# 03_-_CONTROLLER.net
KiCad netlist of a schematic drawn in Altium Designer
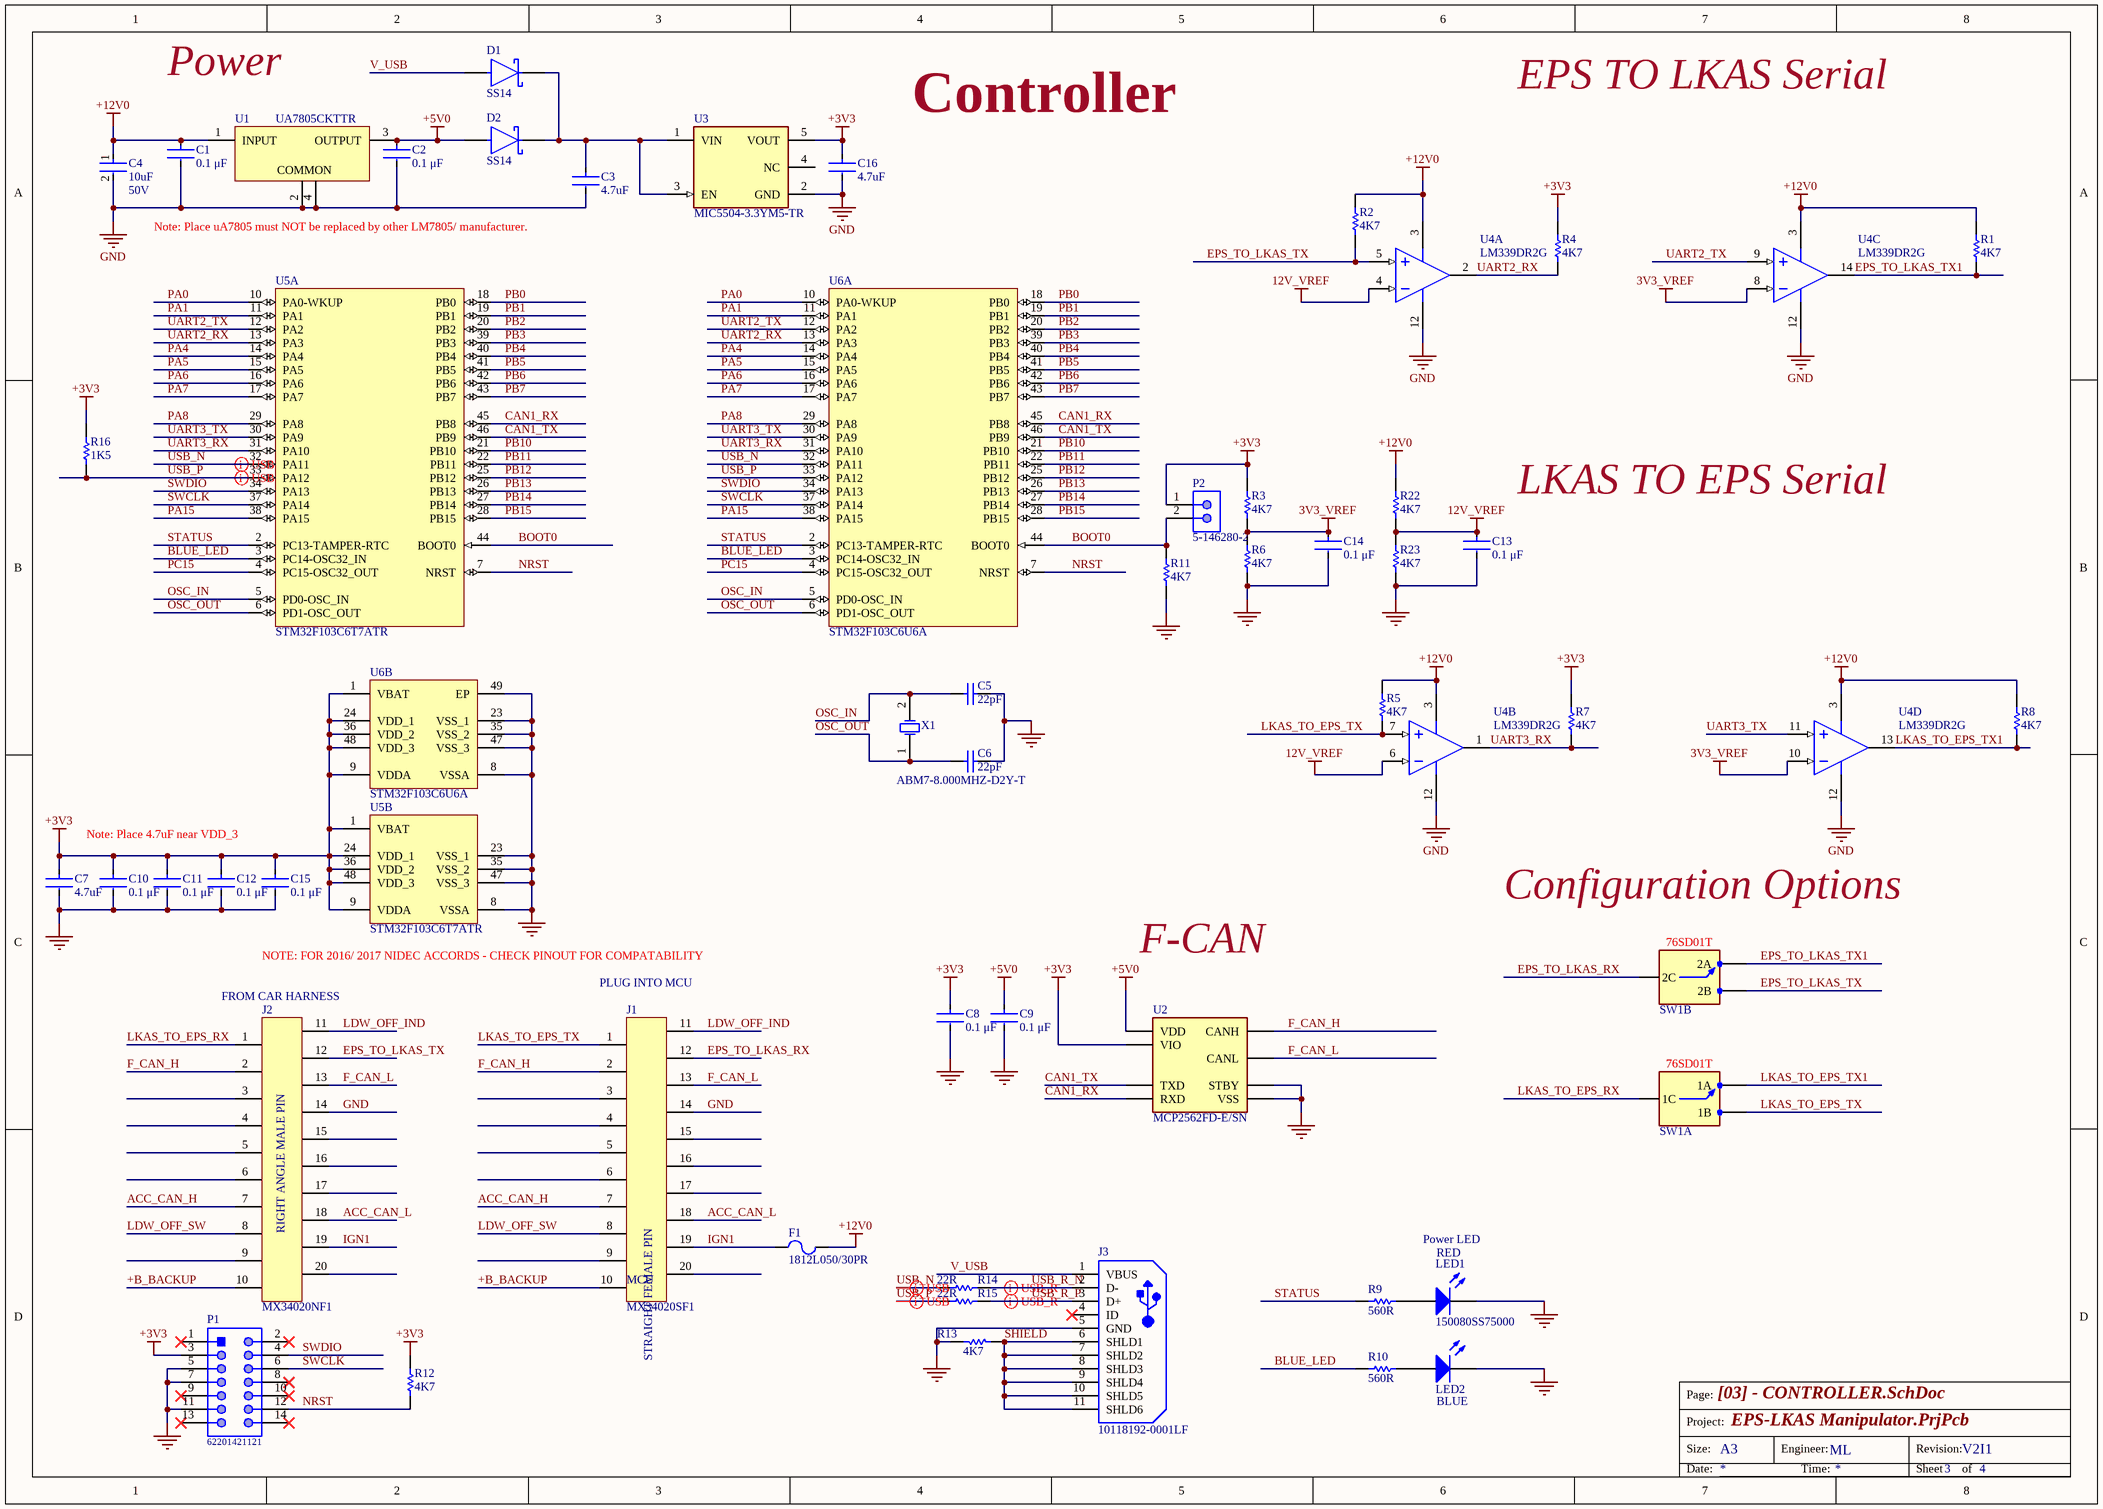
[diagram p0: [03] - CONTROLLER.SchDoc]

(export (version "E")
  (design (tool "Eeschema 10.0.6"))
  (components
    (comp (ref "C1")
      (value "C0603C104M3RACTU")
      (footprint "FP-C0603C-CF-MFG")
      (description "CAP CER 0.1UF 25V X7R 0603")
      (fields
        (field (name "CAPACITANCE") "0.1 μF")
        (field (name "OCTOPART") "https://octopart.com/c0603c104m3ractu-kemet-95914")
        (field (name "MANUFACTURER") "KEMET")
      )
      (libsource (lib "Altium Content Vault") (part "b4654b650e69147ec39a6b967a45e02"))
    )
    (comp (ref "C2")
      (value "C0603C104M3RACTU")
      (footprint "FP-C0603C-CF-MFG")
      (description "CAP CER 0.1UF 25V X7R 0603")
      (fields
        (field (name "CAPACITANCE") "0.1 μF")
        (field (name "OCTOPART") "https://octopart.com/c0603c104m3ractu-kemet-95914")
        (field (name "MANUFACTURER") "KEMET")
      )
      (libsource (lib "Altium Content Vault") (part "b4654b650e69147ec39a6b967a45e02"))
    )
    (comp (ref "C3")
      (value "CL10B475KQ8NQNC")
      (footprint "FP-CL10-IPC_C")
      (description "CAP CER 4.7UF 6.3V X7R 0603")
      (fields
        (field (name "TOLERANCE") "10%")
        (field (name "CAPACITANCE") "4.7uF")
        (field (name "OCTOPART") "https://octopart.com/cl10b475kq8nqnc-samsung-24957976")
      )
      (libsource (lib "Altium Content Vault") (part "11868f565c42a9108669ba33697ecf6"))
    )
    (comp (ref "C4")
      (value "10uF")
      (footprint "FP-CL31-IPC_C")
      (description "CAP CER 10UF 50V X5R 1206")
      (fields
        (field (name "TOLERANCE") "10%")
        (field (name "MANUFACTURER") "Samsung")
        (field (name "VOLTAGE") "50V")
      )
      (libsource (lib "") (part "11868f565c42a9108669ba33697ecf6_1"))
    )
    (comp (ref "C5")
      (value "GRM1885C1H220JA01D")
      (footprint "CAPC1608X90X35ML10T15")
      (description "Chip Capacitor, 22 pF, +/- 5%, 50 V, -55 to 125 degC, 0603 (1608 Metric), RoHS, Tape and Reel")
      (fields (field (name "CAPACITANCE") "22pF") (field (name "MANUFACTURER") "Murata"))
      (libsource (lib "Altium Content Vault") (part "CAP-NP-2"))
    )
    (comp (ref "C6")
      (value "GRM1885C1H220JA01D")
      (footprint "CAPC1608X90X35ML10T15")
      (description "Chip Capacitor, 22 pF, +/- 5%, 50 V, -55 to 125 degC, 0603 (1608 Metric), RoHS, Tape and Reel")
      (fields (field (name "CAPACITANCE") "22pF") (field (name "MANUFACTURER") "Murata"))
      (libsource (lib "Altium Content Vault") (part "CAP-NP-2"))
    )
    (comp (ref "C7")
      (value "CL10B475KQ8NQNC")
      (footprint "FP-CL10-IPC_C")
      (description "CAP CER 4.7UF 6.3V X7R 0603")
      (fields
        (field (name "TOLERANCE") "10%")
        (field (name "CAPACITANCE") "4.7uF")
        (field (name "OCTOPART") "https://octopart.com/cl10b475kq8nqnc-samsung-24957976")
      )
      (libsource (lib "Altium Content Vault") (part "11868f565c42a9108669ba33697ecf6"))
    )
    (comp (ref "C8")
      (value "C0603C104M3RACTU")
      (footprint "FP-C0603C-CF-MFG")
      (description "CAP CER 0.1UF 25V X7R 0603")
      (fields
        (field (name "CAPACITANCE") "0.1 μF")
        (field (name "OCTOPART") "https://octopart.com/c0603c104m3ractu-kemet-95914")
        (field (name "MANUFACTURER") "KEMET")
      )
      (libsource (lib "Altium Content Vault") (part "b4654b650e69147ec39a6b967a45e02"))
    )
    (comp (ref "C9")
      (value "C0603C104M3RACTU")
      (footprint "FP-C0603C-CF-MFG")
      (description "CAP CER 0.1UF 25V X7R 0603")
      (fields
        (field (name "CAPACITANCE") "0.1 μF")
        (field (name "OCTOPART") "https://octopart.com/c0603c104m3ractu-kemet-95914")
        (field (name "MANUFACTURER") "KEMET")
      )
      (libsource (lib "Altium Content Vault") (part "b4654b650e69147ec39a6b967a45e02"))
    )
    (comp (ref "C10")
      (value "C0603C104M3RACTU")
      (footprint "FP-C0603C-CF-MFG")
      (description "CAP CER 0.1UF 25V X7R 0603")
      (fields
        (field (name "CAPACITANCE") "0.1 μF")
        (field (name "OCTOPART") "https://octopart.com/c0603c104m3ractu-kemet-95914")
        (field (name "MANUFACTURER") "KEMET")
      )
      (libsource (lib "Altium Content Vault") (part "b4654b650e69147ec39a6b967a45e02"))
    )
    (comp (ref "C11")
      (value "C0603C104M3RACTU")
      (footprint "FP-C0603C-CF-MFG")
      (description "CAP CER 0.1UF 25V X7R 0603")
      (fields
        (field (name "CAPACITANCE") "0.1 μF")
        (field (name "OCTOPART") "https://octopart.com/c0603c104m3ractu-kemet-95914")
        (field (name "MANUFACTURER") "KEMET")
      )
      (libsource (lib "Altium Content Vault") (part "b4654b650e69147ec39a6b967a45e02"))
    )
    (comp (ref "C12")
      (value "C0603C104M3RACTU")
      (footprint "FP-C0603C-CF-MFG")
      (description "CAP CER 0.1UF 25V X7R 0603")
      (fields
        (field (name "CAPACITANCE") "0.1 μF")
        (field (name "OCTOPART") "https://octopart.com/c0603c104m3ractu-kemet-95914")
        (field (name "MANUFACTURER") "KEMET")
      )
      (libsource (lib "Altium Content Vault") (part "b4654b650e69147ec39a6b967a45e02"))
    )
    (comp (ref "C13")
      (value "C0603C104M3RACTU")
      (footprint "FP-C0603C-CF-MFG")
      (description "CAP CER 0.1UF 25V X7R 0603")
      (fields
        (field (name "CAPACITANCE") "0.1 μF")
        (field (name "OCTOPART") "https://octopart.com/c0603c104m3ractu-kemet-95914")
        (field (name "MANUFACTURER") "KEMET")
      )
      (libsource (lib "Altium Content Vault") (part "b4654b650e69147ec39a6b967a45e02"))
    )
    (comp (ref "C14")
      (value "C0603C104M3RACTU")
      (footprint "FP-C0603C-CF-MFG")
      (description "CAP CER 0.1UF 25V X7R 0603")
      (fields
        (field (name "CAPACITANCE") "0.1 μF")
        (field (name "OCTOPART") "https://octopart.com/c0603c104m3ractu-kemet-95914")
        (field (name "MANUFACTURER") "KEMET")
      )
      (libsource (lib "Altium Content Vault") (part "b4654b650e69147ec39a6b967a45e02"))
    )
    (comp (ref "C15")
      (value "C0603C104M3RACTU")
      (footprint "FP-C0603C-CF-MFG")
      (description "CAP CER 0.1UF 25V X7R 0603")
      (fields
        (field (name "CAPACITANCE") "0.1 μF")
        (field (name "OCTOPART") "https://octopart.com/c0603c104m3ractu-kemet-95914")
        (field (name "MANUFACTURER") "KEMET")
      )
      (libsource (lib "Altium Content Vault") (part "b4654b650e69147ec39a6b967a45e02"))
    )
    (comp (ref "C16")
      (value "CL10B475KQ8NQNC")
      (footprint "FP-CL10-IPC_C")
      (description "CAP CER 4.7UF 6.3V X7R 0603")
      (fields
        (field (name "TOLERANCE") "10%")
        (field (name "CAPACITANCE") "4.7uF")
        (field (name "OCTOPART") "https://octopart.com/cl10b475kq8nqnc-samsung-24957976")
      )
      (libsource (lib "Altium Content Vault") (part "11868f565c42a9108669ba33697ecf6"))
    )
    (comp (ref "D1")
      (value "SS14")
      (footprint "FP-403AE-MFG")
      (description "DIODE SCHOTTKY 40V 1A SMA")
      (fields
        (field (name "MANUFACTURER") "ON Semiconductor")
        (field (name "OCTOPART") "https://octopart.com/ss14-on+semiconductor-29205033")
      )
      (libsource (lib "Altium Content Vault") (part "360ad2f4ac25a952324d13796385471"))
    )
    (comp (ref "D2")
      (value "SS14")
      (footprint "FP-403AE-MFG")
      (description "DIODE SCHOTTKY 40V 1A SMA")
      (fields
        (field (name "MANUFACTURER") "ON Semiconductor")
        (field (name "OCTOPART") "https://octopart.com/ss14-on+semiconductor-29205033")
      )
      (libsource (lib "Altium Content Vault") (part "360ad2f4ac25a952324d13796385471"))
    )
    (comp (ref "F1")
      (value "1812L050/30PR")
      (footprint "LFUS-1812L05030PR_V")
      (description "PTC Resettable Fuse, 0.8 W, 30 V, -40 to 85 degC, 2-Pin SMD, RoHS, Tape and Reel")
      (fields (field (name "MANUFACTURER") "Littelfuse-Inc."))
      (libsource (lib "Altium Content Vault") (part "FUSE-2"))
    )
    (comp (ref "J1")
      (value "MX34020SF1")
      (footprint "MX34020SF1")
      (description "Automotive Connectors Sckt HOUSING 20P")
      (fields (field (name "MANUFACTURER") "JAE Electronics"))
      (libsource (lib "MCU_EPS") (part "MX34020SF1"))
    )
    (comp (ref "J2")
      (value "MX34020NF1")
      (footprint "MX34020NF1")
      (description "JAE MX34 Series, 2.2mm Pitch 20 Way 2 Row Right Angle PCB Header, Solder Termination, 3A")
      (fields (field (name "MANUFACTURER") "JAE Electronics"))
      (libsource (lib "MCU_EPS") (part "MX34020NF1"))
    )
    (comp (ref "J3")
      (value "10118192-0001LF")
      (footprint "FCI-10118192-0001LF-5_V")
      (description "Micro USB B Type Receptacle, -55 to 85 degC, 5-Pin SMD, RoHS, Tape and Reel")
      (fields (field (name "MANUFACTURER") "FCI"))
      (libsource (lib "Altium Content Vault") (part "USB-5-6SHLD"))
    )
    (comp (ref "LED1")
      (value "150080SS75000")
      (footprint "0805_A")
      (description "SMD mono-color Chip LED, WL-SMCW, Super Red")
      (fields (field (name "MANUFACTURER") "Wuerth Elektronik"))
      (libsource (lib "Altium Content Vault") (part "WE-LED_K1A2-2"))
    )
    (comp (ref "LED2")
      (value "150080BS75000")
      (footprint "0805_A")
      (description "SMD mono-color Chip LED, WL-SMCW, Blue")
      (fields (field (name "MANUFACTURER") "Wuerth Elektronik"))
      (libsource (lib "Altium Content Vault") (part "WE-LED_K1A2-2"))
    )
    (comp (ref "P1")
      (value "62201421121")
      (footprint "62201421121")
      (description "THT Vertical Pin Header WR-PHD, Pitch 1.27 mm, Dual Row, 14 pins")
      (fields (field (name "MANUFACTURER") "Wurth Elektronik") (field (name "PUBLISHER") "WurthElektronik"))
      (libsource (lib "Altium Content Vault") (part "WE-CN-2P-M-R14"))
    )
    (comp (ref "P2")
      (value "5-146280-2")
      (footprint "TECO-5-146280-2_V")
      (fields (field (name "MANUFACTURER") "TE Connectivity"))
      (libsource (lib "Altium Content Vault") (part "CN-1P-M-R2"))
    )
    (comp (ref "R1")
      (value "4K7")
      (footprint "R0603")
      (description "Res Thick Film 0603 4.7K Ohm 1% 1/10W 100ppm/C Molded SMD SMD Paper T/R")
      (fields
        (field (name "MANUFACTURER") "Stackpole Electronics")
        (field (name "MANUFACTURER PART NUMBER") "RMCF0603FT4K70")
      )
      (libsource (lib "LKAS_EPS") (part "RMCF0603FT4K70"))
    )
    (comp (ref "R2")
      (value "4K7")
      (footprint "R0603")
      (description "Res Thick Film 0603 4.7K Ohm 1% 1/10W 100ppm/C Molded SMD SMD Paper T/R")
      (fields
        (field (name "MANUFACTURER") "Stackpole Electronics")
        (field (name "MANUFACTURER PART NUMBER") "RMCF0603FT4K70")
      )
      (libsource (lib "LKAS_EPS") (part "RMCF0603FT4K70"))
    )
    (comp (ref "R3")
      (value "4K7")
      (footprint "R0603")
      (description "Res Thick Film 0603 4.7K Ohm 1% 1/10W 100ppm/C Molded SMD SMD Paper T/R")
      (fields
        (field (name "MANUFACTURER") "Stackpole Electronics")
        (field (name "MANUFACTURER PART NUMBER") "RMCF0603FT4K70")
      )
      (libsource (lib "LKAS_EPS") (part "RMCF0603FT4K70"))
    )
    (comp (ref "R4")
      (value "4K7")
      (footprint "R0603")
      (description "Res Thick Film 0603 4.7K Ohm 1% 1/10W 100ppm/C Molded SMD SMD Paper T/R")
      (fields
        (field (name "MANUFACTURER") "Stackpole Electronics")
        (field (name "MANUFACTURER PART NUMBER") "RMCF0603FT4K70")
      )
      (libsource (lib "LKAS_EPS") (part "RMCF0603FT4K70"))
    )
    (comp (ref "R5")
      (value "4K7")
      (footprint "R0603")
      (description "Res Thick Film 0603 4.7K Ohm 1% 1/10W 100ppm/C Molded SMD SMD Paper T/R")
      (fields
        (field (name "MANUFACTURER") "Stackpole Electronics")
        (field (name "MANUFACTURER PART NUMBER") "RMCF0603FT4K70")
      )
      (libsource (lib "LKAS_EPS") (part "RMCF0603FT4K70"))
    )
    (comp (ref "R6")
      (value "4K7")
      (footprint "R0603")
      (description "Res Thick Film 0603 4.7K Ohm 1% 1/10W 100ppm/C Molded SMD SMD Paper T/R")
      (fields
        (field (name "MANUFACTURER") "Stackpole Electronics")
        (field (name "MANUFACTURER PART NUMBER") "RMCF0603FT4K70")
      )
      (libsource (lib "LKAS_EPS") (part "RMCF0603FT4K70"))
    )
    (comp (ref "R7")
      (value "4K7")
      (footprint "R0603")
      (description "Res Thick Film 0603 4.7K Ohm 1% 1/10W 100ppm/C Molded SMD SMD Paper T/R")
      (fields
        (field (name "MANUFACTURER") "Stackpole Electronics")
        (field (name "MANUFACTURER PART NUMBER") "RMCF0603FT4K70")
      )
      (libsource (lib "LKAS_EPS") (part "RMCF0603FT4K70"))
    )
    (comp (ref "R8")
      (value "4K7")
      (footprint "R0603")
      (description "Res Thick Film 0603 4.7K Ohm 1% 1/10W 100ppm/C Molded SMD SMD Paper T/R")
      (fields
        (field (name "MANUFACTURER") "Stackpole Electronics")
        (field (name "MANUFACTURER PART NUMBER") "RMCF0603FT4K70")
      )
      (libsource (lib "LKAS_EPS") (part "RMCF0603FT4K70"))
    )
    (comp (ref "R9")
      (value "RC0603FR-07560RL")
      (footprint "RESC1608X55X25ML10T15")
      (description "Chip Resistor, 560 Ohm, +/- 1%, 0.1 W, -55 to 155 degC, 0603 (1608 Metric), RoHS, Tape and Reel")
      (fields (field (name "RESISTANCE") "560R") (field (name "TOLERANCE") "1%"))
      (libsource (lib "Altium Content Vault") (part "RES-2"))
    )
    (comp (ref "R10")
      (value "RC0603FR-07560RL")
      (footprint "RESC1608X55X25ML10T15")
      (description "Chip Resistor, 560 Ohm, +/- 1%, 0.1 W, -55 to 155 degC, 0603 (1608 Metric), RoHS, Tape and Reel")
      (fields (field (name "RESISTANCE") "560R") (field (name "TOLERANCE") "1%"))
      (libsource (lib "Altium Content Vault") (part "RES-2"))
    )
    (comp (ref "R11")
      (value "4K7")
      (footprint "R0603")
      (description "Res Thick Film 0603 4.7K Ohm 1% 1/10W 100ppm/C Molded SMD SMD Paper T/R")
      (fields
        (field (name "MANUFACTURER") "Stackpole Electronics")
        (field (name "MANUFACTURER PART NUMBER") "RMCF0603FT4K70")
      )
      (libsource (lib "LKAS_EPS") (part "RMCF0603FT4K70"))
    )
    (comp (ref "R12")
      (value "4K7")
      (footprint "R0603")
      (description "Res Thick Film 0603 4.7K Ohm 1% 1/10W 100ppm/C Molded SMD SMD Paper T/R")
      (fields
        (field (name "MANUFACTURER") "Stackpole Electronics")
        (field (name "MANUFACTURER PART NUMBER") "RMCF0603FT4K70")
      )
      (libsource (lib "LKAS_EPS") (part "RMCF0603FT4K70"))
    )
    (comp (ref "R13")
      (value "4K7")
      (footprint "R0603")
      (description "Res Thick Film 0603 4.7K Ohm 1% 1/10W 100ppm/C Molded SMD SMD Paper T/R")
      (fields
        (field (name "MANUFACTURER") "Stackpole Electronics")
        (field (name "MANUFACTURER PART NUMBER") "RMCF0603FT4K70")
      )
      (libsource (lib "LKAS_EPS") (part "RMCF0603FT4K70"))
    )
    (comp (ref "R14")
      (value "22R")
      (footprint "RESC1609X50X30ML10T20")
      (fields (field (name "MANUFACTURER") "Vishay Dale") (field (name "PART NUMBER") "CRCW060322R0JNTA"))
      (libsource (lib "Altium Content Vault") (part "RES"))
    )
    (comp (ref "R15")
      (value "22R")
      (footprint "RESC1609X50X30ML10T20")
      (fields (field (name "MANUFACTURER") "Vishay Dale") (field (name "PART NUMBER") "CRCW060322R0JNTA"))
      (libsource (lib "Altium Content Vault") (part "RES"))
    )
    (comp (ref "R16")
      (value "CRCW06031K50FKTA")
      (footprint "RESC1609X50X30ML10T20")
      (fields (field (name "MANUFACTURER") "Vishay Dale") (field (name "RES") "1K5"))
      (libsource (lib "Altium Content Vault") (part "RES"))
    )
    (comp (ref "R22")
      (value "4K7")
      (footprint "R0603")
      (description "Res Thick Film 0603 4.7K Ohm 1% 1/10W 100ppm/C Molded SMD SMD Paper T/R")
      (fields
        (field (name "MANUFACTURER") "Stackpole Electronics")
        (field (name "MANUFACTURER PART NUMBER") "RMCF0603FT4K70")
      )
      (libsource (lib "LKAS_EPS") (part "RMCF0603FT4K70"))
    )
    (comp (ref "R23")
      (value "4K7")
      (footprint "R0603")
      (description "Res Thick Film 0603 4.7K Ohm 1% 1/10W 100ppm/C Molded SMD SMD Paper T/R")
      (fields
        (field (name "MANUFACTURER") "Stackpole Electronics")
        (field (name "MANUFACTURER PART NUMBER") "RMCF0603FT4K70")
      )
      (libsource (lib "LKAS_EPS") (part "RMCF0603FT4K70"))
    )
    (comp (ref "SW1")
      (value "76STC02T")
      (footprint "76STC02T")
      (description "SWITCH TOGGLE DIP SPDT 150MA 30V\r\nWIRED:\r\n1  2  3\r\n4  5  6")
      (fields (field (name "MANUFACTURER") "Grayhill"))
      (libsource (lib "LKAS_EPS") (part "76STC02T"))
    )
    (comp (ref "U1")
      (value "UA7805CKTTR")
      (footprint "KTT0003A_V")
      (fields (field (name "TOLERANCE") "1%"))
      (libsource (lib "Altium Content Vault") (part "TI-UA78XX-KTT-3"))
    )
    (comp (ref "U2")
      (value "MCP2562FD-E/SN")
      (footprint "MCP2561")
      (description "8 SOIC 3.90mm(.150in) TUBECAN Flexible Data Rate Transceiver")
      (fields (field (name "MANUFACTURER") "Microchip"))
      (libsource (lib "MCU_EPS") (part "MCP2562FD-E/SN"))
    )
    (comp (ref "U3")
      (value "MIC5504-3.3YM5-TR")
      (footprint "FP-SOT23-5LD-PL-1-MFG")
      (description "IC REG LINEAR 3.3V 300MA SOT23-5")
      (libsource (lib "Altium Content Vault") (part "96048095611b4a9579e1e315950d302"))
    )
    (comp (ref "U4")
      (value "LM339DR2G")
      (footprint "ONSC-SOIC-14-751A-03_V")
      (description "Single Supply Quad Comparators, 0 to 70 degC, 14-Pin SOIC, Pb-Free, Tape and Reel")
      (fields (field (name "MANUFACTURER") "On Semiconductor"))
      (libsource (lib "Altium Content Vault") (part "ONSC-LM239_LM339_LM2901_NCV2901_MC3302_LMV339-14"))
    )
    (comp (ref "U5")
      (value "STM32F103C6T7ATR")
      (footprint "STM-LQFP48_L")
      (libsource (lib "Altium Content Vault") (part "MC-ARM-STM32F103X4_6-SQ48"))
    )
    (comp (ref "U6")
      (value "STM32F103C6U6A")
      (footprint "STM-UFQFPN48_M")
      (libsource (lib "Altium Content Vault") (part "MC-ARM-STM32F103X4_6-SQ49"))
    )
    (comp (ref "X1")
      (value "ABM7-8.000MHZ-D2Y-T")
      (footprint "ABRA-ABM7-2_V")
      (description "Microprocessor Crystal, 8 MHz, 18 PF, -40 to 85 degC, 2-Pin SMD, RoHS, Tape and Reel")
      (fields (field (name "MANUFACTURER") "Abracon"))
      (libsource (lib "Altium Content Vault") (part "XTAL_1-2-2"))
    )
  )
  (nets
    (net (code "1") (name "+3V3") (class "Default")
      (node (ref "C10") (pin "1") (pinfunction "1_1") (pintype "passive"))
      (node (ref "C11") (pin "1") (pinfunction "1_1") (pintype "passive"))
      (node (ref "C12") (pin "1") (pinfunction "1_1") (pintype "passive"))
      (node (ref "C15") (pin "1") (pinfunction "1_1") (pintype "passive"))
      (node (ref "C16") (pin "1") (pinfunction "1_1") (pintype "passive"))
      (node (ref "C7") (pin "1") (pinfunction "1_1") (pintype "passive"))
      (node (ref "C8") (pin "1") (pinfunction "1_1") (pintype "passive"))
      (node (ref "P1") (pin "3") (pinfunction "3_3") (pintype "passive"))
      (node (ref "P2") (pin "1") (pinfunction "1_1") (pintype "passive"))
      (node (ref "R12") (pin "2") (pinfunction "2_2") (pintype "passive"))
      (node (ref "R16") (pin "2") (pinfunction "2_2") (pintype "passive"))
      (node (ref "R3") (pin "2") (pinfunction "2_2") (pintype "passive"))
      (node (ref "R4") (pin "2") (pinfunction "2_2") (pintype "passive"))
      (node (ref "R7") (pin "2") (pinfunction "2_2") (pintype "passive"))
      (node (ref "U2") (pin "5") (pinfunction "VIO_5") (pintype "passive"))
      (node (ref "U3") (pin "5") (pinfunction "VOUT_5") (pintype "power_in"))
      (node (ref "U5") (pin "1") (pinfunction "VBAT_1") (pintype "power_in"))
      (node (ref "U5") (pin "24") (pinfunction "VDD_1_24") (pintype "power_in"))
      (node (ref "U5") (pin "36") (pinfunction "VDD_2_36") (pintype "power_in"))
      (node (ref "U5") (pin "48") (pinfunction "VDD_3_48") (pintype "power_in"))
      (node (ref "U5") (pin "9") (pinfunction "VDDA_9") (pintype "power_in"))
      (node (ref "U6") (pin "1") (pinfunction "VBAT_1") (pintype "power_in"))
      (node (ref "U6") (pin "24") (pinfunction "VDD_1_24") (pintype "power_in"))
      (node (ref "U6") (pin "36") (pinfunction "VDD_2_36") (pintype "power_in"))
      (node (ref "U6") (pin "48") (pinfunction "VDD_3_48") (pintype "power_in"))
      (node (ref "U6") (pin "9") (pinfunction "VDDA_9") (pintype "power_in"))
    )
    (net (code "2") (name "+5V0") (class "Default")
      (node (ref "C2") (pin "1") (pinfunction "1_1") (pintype "passive"))
      (node (ref "C9") (pin "1") (pinfunction "1_1") (pintype "passive"))
      (node (ref "D2") (pin "1") (pinfunction "A_1") (pintype "passive"))
      (node (ref "U1") (pin "3") (pinfunction "OUTPUT_3") (pintype "power_in"))
      (node (ref "U2") (pin "3") (pinfunction "VDD_3") (pintype "passive"))
    )
    (net (code "3") (name "+12V0") (class "Default")
      (node (ref "C1") (pin "1") (pinfunction "1_1") (pintype "passive"))
      (node (ref "C4") (pin "1") (pinfunction "1_1") (pintype "passive"))
      (node (ref "F1") (pin "2") (pinfunction "2_2") (pintype "passive"))
      (node (ref "R1") (pin "2") (pinfunction "2_2") (pintype "passive"))
      (node (ref "R2") (pin "2") (pinfunction "2_2") (pintype "passive"))
      (node (ref "R22") (pin "2") (pinfunction "2_2") (pintype "passive"))
      (node (ref "R5") (pin "2") (pinfunction "2_2") (pintype "passive"))
      (node (ref "R8") (pin "2") (pinfunction "2_2") (pintype "passive"))
      (node (ref "U1") (pin "1") (pinfunction "INPUT_1") (pintype "power_in"))
      (node (ref "U4") (pin "3") (pinfunction "VCC_3") (pintype "power_in"))
    )
    (net (code "4") (name "/+B_BACKUP") (class "Default")
      (node (ref "J1") (pin "10") (pinfunction "10_10") (pintype "passive"))
      (node (ref "J2") (pin "10") (pinfunction "10_10") (pintype "passive"))
    )
    (net (code "5") (name "/ACC_CAN_H") (class "Default")
      (node (ref "J1") (pin "7") (pinfunction "7_7") (pintype "passive"))
      (node (ref "J2") (pin "7") (pinfunction "7_7") (pintype "passive"))
    )
    (net (code "6") (name "/ACC_CAN_L") (class "Default")
      (node (ref "J1") (pin "18") (pinfunction "18_18") (pintype "passive"))
      (node (ref "J2") (pin "18") (pinfunction "18_18") (pintype "passive"))
    )
    (net (code "7") (name "/BLUE_LED") (class "Default")
      (node (ref "R10") (pin "1") (pinfunction "1_1") (pintype "passive"))
      (node (ref "U5") (pin "3") (pinfunction "PC14-OSC32_IN_3") (pintype "bidirectional"))
      (node (ref "U6") (pin "3") (pinfunction "PC14-OSC32_IN_3") (pintype "bidirectional"))
    )
    (net (code "8") (name "/BOOT0") (class "Default")
      (node (ref "P2") (pin "2") (pinfunction "2_2") (pintype "passive"))
      (node (ref "R11") (pin "2") (pinfunction "2_2") (pintype "passive"))
      (node (ref "U5") (pin "44") (pinfunction "BOOT0_44") (pintype "input"))
      (node (ref "U6") (pin "44") (pinfunction "BOOT0_44") (pintype "input"))
    )
    (net (code "9") (name "/CAN1_RX") (class "Default")
      (node (ref "U2") (pin "4") (pinfunction "RXD_4") (pintype "passive"))
      (node (ref "U5") (pin "45") (pinfunction "PB8_45") (pintype "bidirectional"))
      (node (ref "U6") (pin "45") (pinfunction "PB8_45") (pintype "bidirectional"))
    )
    (net (code "10") (name "/CAN1_TX") (class "Default")
      (node (ref "U2") (pin "1") (pinfunction "TXD_1") (pintype "passive"))
      (node (ref "U5") (pin "46") (pinfunction "PB9_46") (pintype "bidirectional"))
      (node (ref "U6") (pin "46") (pinfunction "PB9_46") (pintype "bidirectional"))
    )
    (net (code "11") (name "/EPS_TO_LKAS_RX") (class "Default")
      (node (ref "J1") (pin "12") (pinfunction "12_12") (pintype "passive"))
      (node (ref "SW1") (pin "C2") (pinfunction "2C_C2") (pintype "passive"))
    )
    (net (code "12") (name "/EPS_TO_LKAS_TX") (class "Default")
      (node (ref "J2") (pin "12") (pinfunction "12_12") (pintype "passive"))
      (node (ref "R2") (pin "1") (pinfunction "1_1") (pintype "passive"))
      (node (ref "SW1") (pin "2B") (pinfunction "2B_2B") (pintype "passive"))
      (node (ref "U4") (pin "5") (pinfunction "IN1+_5") (pintype "input"))
    )
    (net (code "13") (name "/EPS_TO_LKAS_TX1") (class "Default")
      (node (ref "R1") (pin "1") (pinfunction "1_1") (pintype "passive"))
      (node (ref "SW1") (pin "2A") (pinfunction "2A_2A") (pintype "passive"))
      (node (ref "U4") (pin "14") (pinfunction "OUT3_14") (pintype "open_collector"))
    )
    (net (code "14") (name "/F_CAN_H") (class "Default")
      (node (ref "J1") (pin "2") (pinfunction "2_2") (pintype "passive"))
      (node (ref "J2") (pin "2") (pinfunction "2_2") (pintype "passive"))
      (node (ref "U2") (pin "7") (pinfunction "CANH_7") (pintype "passive"))
    )
    (net (code "15") (name "/F_CAN_L") (class "Default")
      (node (ref "J1") (pin "13") (pinfunction "13_13") (pintype "passive"))
      (node (ref "J2") (pin "13") (pinfunction "13_13") (pintype "passive"))
      (node (ref "U2") (pin "6") (pinfunction "CANL_6") (pintype "passive"))
    )
    (net (code "16") (name "/IGN1") (class "Default")
      (node (ref "F1") (pin "1") (pinfunction "1_1") (pintype "passive"))
      (node (ref "J1") (pin "19") (pinfunction "19_19") (pintype "passive"))
      (node (ref "J2") (pin "19") (pinfunction "19_19") (pintype "passive"))
    )
    (net (code "17") (name "/LDW_OFF_IND") (class "Default")
      (node (ref "J1") (pin "11") (pinfunction "11_11") (pintype "passive"))
      (node (ref "J2") (pin "11") (pinfunction "11_11") (pintype "passive"))
    )
    (net (code "18") (name "/LDW_OFF_SW") (class "Default")
      (node (ref "J1") (pin "8") (pinfunction "8_8") (pintype "passive"))
      (node (ref "J2") (pin "8") (pinfunction "8_8") (pintype "passive"))
    )
    (net (code "19") (name "/LKAS_TO_EPS_RX") (class "Default")
      (node (ref "J2") (pin "1") (pinfunction "1_1") (pintype "passive"))
      (node (ref "SW1") (pin "C1") (pinfunction "1C_C1") (pintype "passive"))
    )
    (net (code "20") (name "/LKAS_TO_EPS_TX") (class "Default")
      (node (ref "J1") (pin "1") (pinfunction "1_1") (pintype "passive"))
      (node (ref "R5") (pin "1") (pinfunction "1_1") (pintype "passive"))
      (node (ref "SW1") (pin "1B") (pinfunction "1B_1B") (pintype "passive"))
      (node (ref "U4") (pin "7") (pinfunction "IN2+_7") (pintype "input"))
    )
    (net (code "21") (name "/LKAS_TO_EPS_TX1") (class "Default")
      (node (ref "R8") (pin "1") (pinfunction "1_1") (pintype "passive"))
      (node (ref "SW1") (pin "1A") (pinfunction "1A_1A") (pintype "passive"))
      (node (ref "U4") (pin "13") (pinfunction "OUT4_13") (pintype "open_collector"))
    )
    (net (code "22") (name "/NRST") (class "Default")
      (node (ref "P1") (pin "12") (pinfunction "12_12") (pintype "passive"))
      (node (ref "R12") (pin "1") (pinfunction "1_1") (pintype "passive"))
      (node (ref "U5") (pin "7") (pinfunction "NRST_7") (pintype "bidirectional"))
      (node (ref "U6") (pin "7") (pinfunction "NRST_7") (pintype "bidirectional"))
    )
    (net (code "23") (name "/OSC_IN") (class "Default")
      (node (ref "C5") (pin "1") (pinfunction "1_1") (pintype "passive"))
      (node (ref "U5") (pin "5") (pinfunction "PD0-OSC_IN_5") (pintype "bidirectional"))
      (node (ref "U6") (pin "5") (pinfunction "PD0-OSC_IN_5") (pintype "bidirectional"))
      (node (ref "X1") (pin "2") (pinfunction "X2_2") (pintype "passive"))
    )
    (net (code "24") (name "/OSC_OUT") (class "Default")
      (node (ref "C6") (pin "1") (pinfunction "1_1") (pintype "passive"))
      (node (ref "U5") (pin "6") (pinfunction "PD1-OSC_OUT_6") (pintype "bidirectional"))
      (node (ref "U6") (pin "6") (pinfunction "PD1-OSC_OUT_6") (pintype "bidirectional"))
      (node (ref "X1") (pin "1") (pinfunction "X1_1") (pintype "passive"))
    )
    (net (code "25") (name "/PA0") (class "Default")
      (node (ref "U5") (pin "10") (pinfunction "PA0-WKUP_10") (pintype "bidirectional"))
      (node (ref "U6") (pin "10") (pinfunction "PA0-WKUP_10") (pintype "bidirectional"))
    )
    (net (code "26") (name "/PA1") (class "Default")
      (node (ref "U5") (pin "11") (pinfunction "PA1_11") (pintype "bidirectional"))
      (node (ref "U6") (pin "11") (pinfunction "PA1_11") (pintype "bidirectional"))
    )
    (net (code "27") (name "/PA4") (class "Default")
      (node (ref "U5") (pin "14") (pinfunction "PA4_14") (pintype "bidirectional"))
      (node (ref "U6") (pin "14") (pinfunction "PA4_14") (pintype "bidirectional"))
    )
    (net (code "28") (name "/PA5") (class "Default")
      (node (ref "U5") (pin "15") (pinfunction "PA5_15") (pintype "bidirectional"))
      (node (ref "U6") (pin "15") (pinfunction "PA5_15") (pintype "bidirectional"))
    )
    (net (code "29") (name "/PA6") (class "Default")
      (node (ref "U5") (pin "16") (pinfunction "PA6_16") (pintype "bidirectional"))
      (node (ref "U6") (pin "16") (pinfunction "PA6_16") (pintype "bidirectional"))
    )
    (net (code "30") (name "/PA7") (class "Default")
      (node (ref "U5") (pin "17") (pinfunction "PA7_17") (pintype "bidirectional"))
      (node (ref "U6") (pin "17") (pinfunction "PA7_17") (pintype "bidirectional"))
    )
    (net (code "31") (name "/PA8") (class "Default")
      (node (ref "U5") (pin "29") (pinfunction "PA8_29") (pintype "bidirectional"))
      (node (ref "U6") (pin "29") (pinfunction "PA8_29") (pintype "bidirectional"))
    )
    (net (code "32") (name "/PA15") (class "Default")
      (node (ref "U5") (pin "38") (pinfunction "PA15_38") (pintype "bidirectional"))
      (node (ref "U6") (pin "38") (pinfunction "PA15_38") (pintype "bidirectional"))
    )
    (net (code "33") (name "/PB0") (class "Default")
      (node (ref "U5") (pin "18") (pinfunction "PB0_18") (pintype "bidirectional"))
      (node (ref "U6") (pin "18") (pinfunction "PB0_18") (pintype "bidirectional"))
    )
    (net (code "34") (name "/PB1") (class "Default")
      (node (ref "U5") (pin "19") (pinfunction "PB1_19") (pintype "bidirectional"))
      (node (ref "U6") (pin "19") (pinfunction "PB1_19") (pintype "bidirectional"))
    )
    (net (code "35") (name "/PB2") (class "Default")
      (node (ref "U5") (pin "20") (pinfunction "PB2_20") (pintype "bidirectional"))
      (node (ref "U6") (pin "20") (pinfunction "PB2_20") (pintype "bidirectional"))
    )
    (net (code "36") (name "/PB3") (class "Default")
      (node (ref "U5") (pin "39") (pinfunction "PB3_39") (pintype "bidirectional"))
      (node (ref "U6") (pin "39") (pinfunction "PB3_39") (pintype "bidirectional"))
    )
    (net (code "37") (name "/PB4") (class "Default")
      (node (ref "U5") (pin "40") (pinfunction "PB4_40") (pintype "bidirectional"))
      (node (ref "U6") (pin "40") (pinfunction "PB4_40") (pintype "bidirectional"))
    )
    (net (code "38") (name "/PB5") (class "Default")
      (node (ref "U5") (pin "41") (pinfunction "PB5_41") (pintype "bidirectional"))
      (node (ref "U6") (pin "41") (pinfunction "PB5_41") (pintype "bidirectional"))
    )
    (net (code "39") (name "/PB6") (class "Default")
      (node (ref "U5") (pin "42") (pinfunction "PB6_42") (pintype "bidirectional"))
      (node (ref "U6") (pin "42") (pinfunction "PB6_42") (pintype "bidirectional"))
    )
    (net (code "40") (name "/PB7") (class "Default")
      (node (ref "U5") (pin "43") (pinfunction "PB7_43") (pintype "bidirectional"))
      (node (ref "U6") (pin "43") (pinfunction "PB7_43") (pintype "bidirectional"))
    )
    (net (code "41") (name "/PB10") (class "Default")
      (node (ref "U5") (pin "21") (pinfunction "PB10_21") (pintype "bidirectional"))
      (node (ref "U6") (pin "21") (pinfunction "PB10_21") (pintype "bidirectional"))
    )
    (net (code "42") (name "/PB11") (class "Default")
      (node (ref "U5") (pin "22") (pinfunction "PB11_22") (pintype "bidirectional"))
      (node (ref "U6") (pin "22") (pinfunction "PB11_22") (pintype "bidirectional"))
    )
    (net (code "43") (name "/PB12") (class "Default")
      (node (ref "U5") (pin "25") (pinfunction "PB12_25") (pintype "bidirectional"))
      (node (ref "U6") (pin "25") (pinfunction "PB12_25") (pintype "bidirectional"))
    )
    (net (code "44") (name "/PB13") (class "Default")
      (node (ref "U5") (pin "26") (pinfunction "PB13_26") (pintype "bidirectional"))
      (node (ref "U6") (pin "26") (pinfunction "PB13_26") (pintype "bidirectional"))
    )
    (net (code "45") (name "/PB14") (class "Default")
      (node (ref "U5") (pin "27") (pinfunction "PB14_27") (pintype "bidirectional"))
      (node (ref "U6") (pin "27") (pinfunction "PB14_27") (pintype "bidirectional"))
    )
    (net (code "46") (name "/PB15") (class "Default")
      (node (ref "U5") (pin "28") (pinfunction "PB15_28") (pintype "bidirectional"))
      (node (ref "U6") (pin "28") (pinfunction "PB15_28") (pintype "bidirectional"))
    )
    (net (code "47") (name "/PC15") (class "Default")
      (node (ref "U5") (pin "4") (pinfunction "PC15-OSC32_OUT_4") (pintype "bidirectional"))
      (node (ref "U6") (pin "4") (pinfunction "PC15-OSC32_OUT_4") (pintype "bidirectional"))
    )
    (net (code "48") (name "/SHIELD") (class "Default")
      (node (ref "J3") (pin "10") (pinfunction "SHLD5_10") (pintype "passive"))
      (node (ref "J3") (pin "11") (pinfunction "SHLD6_11") (pintype "passive"))
      (node (ref "J3") (pin "6") (pinfunction "SHLD1_6") (pintype "passive"))
      (node (ref "J3") (pin "7") (pinfunction "SHLD2_7") (pintype "passive"))
      (node (ref "J3") (pin "8") (pinfunction "SHLD3_8") (pintype "passive"))
      (node (ref "J3") (pin "9") (pinfunction "SHLD4_9") (pintype "passive"))
      (node (ref "R13") (pin "1") (pinfunction "1_1") (pintype "passive"))
    )
    (net (code "49") (name "/STATUS") (class "Default")
      (node (ref "R9") (pin "1") (pinfunction "1_1") (pintype "passive"))
      (node (ref "U5") (pin "2") (pinfunction "PC13-TAMPER-RTC_2") (pintype "bidirectional"))
      (node (ref "U6") (pin "2") (pinfunction "PC13-TAMPER-RTC_2") (pintype "bidirectional"))
    )
    (net (code "50") (name "/SWCLK") (class "Default")
      (node (ref "P1") (pin "6") (pinfunction "6_6") (pintype "passive"))
      (node (ref "U5") (pin "37") (pinfunction "PA14_37") (pintype "bidirectional"))
      (node (ref "U6") (pin "37") (pinfunction "PA14_37") (pintype "bidirectional"))
    )
    (net (code "51") (name "/SWDIO") (class "Default")
      (node (ref "P1") (pin "4") (pinfunction "4_4") (pintype "passive"))
      (node (ref "U5") (pin "34") (pinfunction "PA13_34") (pintype "bidirectional"))
      (node (ref "U6") (pin "34") (pinfunction "PA13_34") (pintype "bidirectional"))
    )
    (net (code "52") (name "/UART2_RX") (class "Default")
      (node (ref "R4") (pin "1") (pinfunction "1_1") (pintype "passive"))
      (node (ref "U4") (pin "2") (pinfunction "OUT1_2") (pintype "open_collector"))
      (node (ref "U5") (pin "13") (pinfunction "PA3_13") (pintype "bidirectional"))
      (node (ref "U6") (pin "13") (pinfunction "PA3_13") (pintype "bidirectional"))
    )
    (net (code "53") (name "/UART2_TX") (class "Default")
      (node (ref "U4") (pin "9") (pinfunction "IN3+_9") (pintype "input"))
      (node (ref "U5") (pin "12") (pinfunction "PA2_12") (pintype "bidirectional"))
      (node (ref "U6") (pin "12") (pinfunction "PA2_12") (pintype "bidirectional"))
    )
    (net (code "54") (name "/UART3_RX") (class "Default")
      (node (ref "R7") (pin "1") (pinfunction "1_1") (pintype "passive"))
      (node (ref "U4") (pin "1") (pinfunction "OUT2_1") (pintype "open_collector"))
      (node (ref "U5") (pin "31") (pinfunction "PA10_31") (pintype "bidirectional"))
      (node (ref "U6") (pin "31") (pinfunction "PA10_31") (pintype "bidirectional"))
    )
    (net (code "55") (name "/UART3_TX") (class "Default")
      (node (ref "U4") (pin "11") (pinfunction "IN4+_11") (pintype "input"))
      (node (ref "U5") (pin "30") (pinfunction "PA9_30") (pintype "bidirectional"))
      (node (ref "U6") (pin "30") (pinfunction "PA9_30") (pintype "bidirectional"))
    )
    (net (code "56") (name "/USB_N") (class "Default")
      (node (ref "R14") (pin "1") (pinfunction "1_1") (pintype "passive"))
      (node (ref "U5") (pin "32") (pinfunction "PA11_32") (pintype "bidirectional"))
      (node (ref "U6") (pin "32") (pinfunction "PA11_32") (pintype "bidirectional"))
    )
    (net (code "57") (name "/USB_P") (class "Default")
      (node (ref "R15") (pin "1") (pinfunction "1_1") (pintype "passive"))
      (node (ref "R16") (pin "1") (pinfunction "1_1") (pintype "passive"))
      (node (ref "U5") (pin "33") (pinfunction "PA12_33") (pintype "bidirectional"))
      (node (ref "U6") (pin "33") (pinfunction "PA12_33") (pintype "bidirectional"))
    )
    (net (code "58") (name "/USB_R_N") (class "Default")
      (node (ref "J3") (pin "2") (pinfunction "D-_2") (pintype "passive"))
      (node (ref "R14") (pin "2") (pinfunction "2_2") (pintype "passive"))
    )
    (net (code "59") (name "/USB_R_P") (class "Default")
      (node (ref "J3") (pin "3") (pinfunction "D+_3") (pintype "passive"))
      (node (ref "R15") (pin "2") (pinfunction "2_2") (pintype "passive"))
    )
    (net (code "60") (name "/V_USB") (class "Default")
      (node (ref "D1") (pin "1") (pinfunction "A_1") (pintype "passive"))
      (node (ref "J3") (pin "1") (pinfunction "VBUS_1") (pintype "passive"))
    )
    (net (code "61") (name "3V3_VREF") (class "Default")
      (node (ref "C14") (pin "1") (pinfunction "1_1") (pintype "passive"))
      (node (ref "R3") (pin "1") (pinfunction "1_1") (pintype "passive"))
      (node (ref "R6") (pin "2") (pinfunction "2_2") (pintype "passive"))
      (node (ref "U4") (pin "10") (pinfunction "IN4-_10") (pintype "input"))
      (node (ref "U4") (pin "8") (pinfunction "IN3-_8") (pintype "input"))
    )
    (net (code "62") (name "12V_VREF") (class "Default")
      (node (ref "C13") (pin "1") (pinfunction "1_1") (pintype "passive"))
      (node (ref "R22") (pin "1") (pinfunction "1_1") (pintype "passive"))
      (node (ref "R23") (pin "2") (pinfunction "2_2") (pintype "passive"))
      (node (ref "U4") (pin "4") (pinfunction "IN1-_4") (pintype "input"))
      (node (ref "U4") (pin "6") (pinfunction "IN2-_6") (pintype "input"))
    )
    (net (code "63") (name "GND") (class "Default")
      (node (ref "C1") (pin "2") (pinfunction "2_2") (pintype "passive"))
      (node (ref "C10") (pin "2") (pinfunction "2_2") (pintype "passive"))
      (node (ref "C11") (pin "2") (pinfunction "2_2") (pintype "passive"))
      (node (ref "C12") (pin "2") (pinfunction "2_2") (pintype "passive"))
      (node (ref "C13") (pin "2") (pinfunction "2_2") (pintype "passive"))
      (node (ref "C14") (pin "2") (pinfunction "2_2") (pintype "passive"))
      (node (ref "C15") (pin "2") (pinfunction "2_2") (pintype "passive"))
      (node (ref "C16") (pin "2") (pinfunction "2_2") (pintype "passive"))
      (node (ref "C2") (pin "2") (pinfunction "2_2") (pintype "passive"))
      (node (ref "C3") (pin "2") (pinfunction "2_2") (pintype "passive"))
      (node (ref "C4") (pin "2") (pinfunction "2_2") (pintype "passive"))
      (node (ref "C5") (pin "2") (pinfunction "2_2") (pintype "passive"))
      (node (ref "C6") (pin "2") (pinfunction "2_2") (pintype "passive"))
      (node (ref "C7") (pin "2") (pinfunction "2_2") (pintype "passive"))
      (node (ref "C8") (pin "2") (pinfunction "2_2") (pintype "passive"))
      (node (ref "C9") (pin "2") (pinfunction "2_2") (pintype "passive"))
      (node (ref "J1") (pin "14") (pinfunction "14_14") (pintype "passive"))
      (node (ref "J2") (pin "14") (pinfunction "14_14") (pintype "passive"))
      (node (ref "J3") (pin "5") (pinfunction "GND_5") (pintype "passive"))
      (node (ref "LED1") (pin "1") (pinfunction "K_1") (pintype "passive"))
      (node (ref "LED2") (pin "1") (pinfunction "K_1") (pintype "passive"))
      (node (ref "P1") (pin "11") (pinfunction "11_11") (pintype "passive"))
      (node (ref "P1") (pin "5") (pinfunction "5_5") (pintype "passive"))
      (node (ref "P1") (pin "7") (pinfunction "7_7") (pintype "passive"))
      (node (ref "R11") (pin "1") (pinfunction "1_1") (pintype "passive"))
      (node (ref "R13") (pin "2") (pinfunction "2_2") (pintype "passive"))
      (node (ref "R23") (pin "1") (pinfunction "1_1") (pintype "passive"))
      (node (ref "R6") (pin "1") (pinfunction "1_1") (pintype "passive"))
      (node (ref "U1") (pin "2") (pinfunction "COMMON_2") (pintype "power_in"))
      (node (ref "U1") (pin "4") (pinfunction "COMMON_4") (pintype "power_in"))
      (node (ref "U2") (pin "2") (pinfunction "VSS_2") (pintype "passive"))
      (node (ref "U2") (pin "8") (pinfunction "STBY_8") (pintype "passive"))
      (node (ref "U3") (pin "2") (pinfunction "GND_2") (pintype "power_in"))
      (node (ref "U4") (pin "12") (pinfunction "GND_12") (pintype "power_in"))
      (node (ref "U5") (pin "23") (pinfunction "VSS_1_23") (pintype "power_in"))
      (node (ref "U5") (pin "35") (pinfunction "VSS_2_35") (pintype "power_in"))
      (node (ref "U5") (pin "47") (pinfunction "VSS_3_47") (pintype "power_in"))
      (node (ref "U5") (pin "8") (pinfunction "VSSA_8") (pintype "power_in"))
      (node (ref "U6") (pin "23") (pinfunction "VSS_1_23") (pintype "power_in"))
      (node (ref "U6") (pin "35") (pinfunction "VSS_2_35") (pintype "power_in"))
      (node (ref "U6") (pin "47") (pinfunction "VSS_3_47") (pintype "power_in"))
      (node (ref "U6") (pin "49") (pinfunction "EP_49") (pintype "power_in"))
      (node (ref "U6") (pin "8") (pinfunction "VSSA_8") (pintype "power_in"))
    )
    (net (code "64") (name "Net-(D1-C)") (class "Default")
      (node (ref "C3") (pin "1") (pinfunction "1_1") (pintype "passive"))
      (node (ref "D1") (pin "2") (pinfunction "C_2") (pintype "passive"))
      (node (ref "D2") (pin "2") (pinfunction "C_2") (pintype "passive"))
      (node (ref "U3") (pin "1") (pinfunction "VIN_1") (pintype "power_in"))
      (node (ref "U3") (pin "3") (pinfunction "EN_3") (pintype "input"))
    )
    (net (code "65") (name "Net-(LED1-A)") (class "Default")
      (node (ref "LED1") (pin "2") (pinfunction "A_2") (pintype "passive"))
      (node (ref "R9") (pin "2") (pinfunction "2_2") (pintype "passive"))
    )
    (net (code "66") (name "Net-(LED2-A)") (class "Default")
      (node (ref "LED2") (pin "2") (pinfunction "A_2") (pintype "passive"))
      (node (ref "R10") (pin "2") (pinfunction "2_2") (pintype "passive"))
    )
    (net (code "67") (name "unconnected-(J1-Pad3)") (class "Default")
      (node (ref "J1") (pin "3") (pinfunction "3_3") (pintype "passive"))
    )
    (net (code "68") (name "unconnected-(J1-Pad4)") (class "Default")
      (node (ref "J1") (pin "4") (pinfunction "4_4") (pintype "passive"))
    )
    (net (code "69") (name "unconnected-(J1-Pad5)") (class "Default")
      (node (ref "J1") (pin "5") (pinfunction "5_5") (pintype "passive"))
    )
    (net (code "70") (name "unconnected-(J1-Pad6)") (class "Default")
      (node (ref "J1") (pin "6") (pinfunction "6_6") (pintype "passive"))
    )
    (net (code "71") (name "unconnected-(J1-Pad9)") (class "Default")
      (node (ref "J1") (pin "9") (pinfunction "9_9") (pintype "passive"))
    )
    (net (code "72") (name "unconnected-(J1-Pad15)") (class "Default")
      (node (ref "J1") (pin "15") (pinfunction "15_15") (pintype "passive"))
    )
    (net (code "73") (name "unconnected-(J1-Pad16)") (class "Default")
      (node (ref "J1") (pin "16") (pinfunction "16_16") (pintype "passive"))
    )
    (net (code "74") (name "unconnected-(J1-Pad17)") (class "Default")
      (node (ref "J1") (pin "17") (pinfunction "17_17") (pintype "passive"))
    )
    (net (code "75") (name "unconnected-(J1-Pad20)") (class "Default")
      (node (ref "J1") (pin "20") (pinfunction "20_20") (pintype "passive"))
    )
    (net (code "76") (name "unconnected-(J2-Pad3)") (class "Default")
      (node (ref "J2") (pin "3") (pinfunction "3_3") (pintype "passive"))
    )
    (net (code "77") (name "unconnected-(J2-Pad4)") (class "Default")
      (node (ref "J2") (pin "4") (pinfunction "4_4") (pintype "passive"))
    )
    (net (code "78") (name "unconnected-(J2-Pad5)") (class "Default")
      (node (ref "J2") (pin "5") (pinfunction "5_5") (pintype "passive"))
    )
    (net (code "79") (name "unconnected-(J2-Pad6)") (class "Default")
      (node (ref "J2") (pin "6") (pinfunction "6_6") (pintype "passive"))
    )
    (net (code "80") (name "unconnected-(J2-Pad9)") (class "Default")
      (node (ref "J2") (pin "9") (pinfunction "9_9") (pintype "passive"))
    )
    (net (code "81") (name "unconnected-(J2-Pad15)") (class "Default")
      (node (ref "J2") (pin "15") (pinfunction "15_15") (pintype "passive"))
    )
    (net (code "82") (name "unconnected-(J2-Pad16)") (class "Default")
      (node (ref "J2") (pin "16") (pinfunction "16_16") (pintype "passive"))
    )
    (net (code "83") (name "unconnected-(J2-Pad17)") (class "Default")
      (node (ref "J2") (pin "17") (pinfunction "17_17") (pintype "passive"))
    )
    (net (code "84") (name "unconnected-(J2-Pad20)") (class "Default")
      (node (ref "J2") (pin "20") (pinfunction "20_20") (pintype "passive"))
    )
    (net (code "85") (name "unconnected-(J3-ID-Pad4)") (class "Default")
      (node (ref "J3") (pin "4") (pinfunction "ID_4") (pintype "passive+no_connect"))
    )
    (net (code "86") (name "unconnected-(P1-Pad1)") (class "Default")
      (node (ref "P1") (pin "1") (pinfunction "1_1") (pintype "passive+no_connect"))
    )
    (net (code "87") (name "unconnected-(P1-Pad2)") (class "Default")
      (node (ref "P1") (pin "2") (pinfunction "2_2") (pintype "passive+no_connect"))
    )
    (net (code "88") (name "unconnected-(P1-Pad8)") (class "Default")
      (node (ref "P1") (pin "8") (pinfunction "8_8") (pintype "passive+no_connect"))
    )
    (net (code "89") (name "unconnected-(P1-Pad9)") (class "Default")
      (node (ref "P1") (pin "9") (pinfunction "9_9") (pintype "passive+no_connect"))
    )
    (net (code "90") (name "unconnected-(P1-Pad10)") (class "Default")
      (node (ref "P1") (pin "10") (pinfunction "10_10") (pintype "passive+no_connect"))
    )
    (net (code "91") (name "unconnected-(P1-Pad13)") (class "Default")
      (node (ref "P1") (pin "13") (pinfunction "13_13") (pintype "passive+no_connect"))
    )
    (net (code "92") (name "unconnected-(P1-Pad14)") (class "Default")
      (node (ref "P1") (pin "14") (pinfunction "14_14") (pintype "passive+no_connect"))
    )
    (net (code "93") (name "unconnected-(U3-NC-Pad4)") (class "Default")
      (node (ref "U3") (pin "4") (pinfunction "NC_4") (pintype "passive"))
    )
  )
)
